# EaglePCBWorkshop.net
KiCad netlist of a schematic drawn in EAGLE
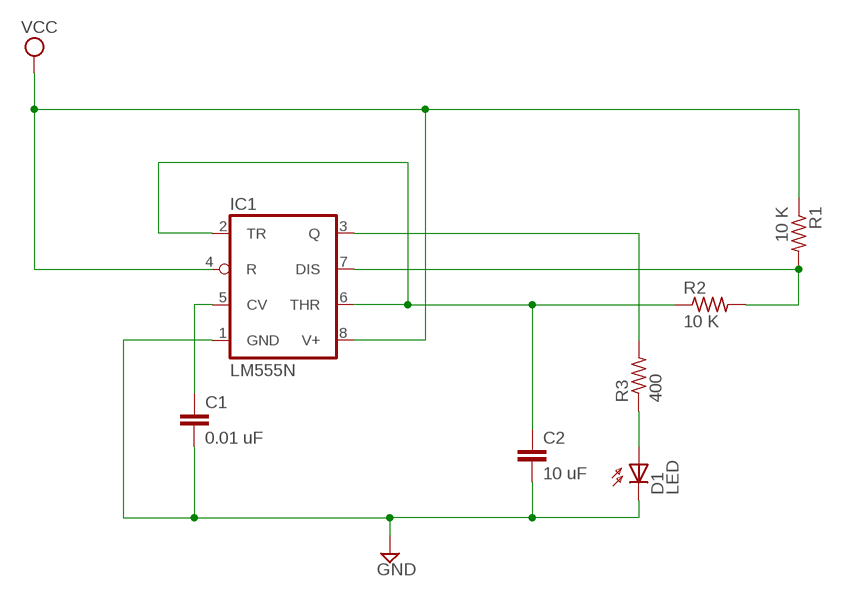
[diagram p0: schematic, sheet 1]

(export (version "E")
  (design (tool "Eeschema 10.0.6"))
  (components
    (comp (ref "C1")
      (value "0.01 uF")
      (footprint "eagle-import:C5B2.5")
      (libsource (lib "eagle-import") (part "C5/2.5"))
    )
    (comp (ref "C2")
      (value "10 uF")
      (footprint "eagle-import:C5B2.5")
      (libsource (lib "eagle-import") (part "C5/2.5"))
    )
    (comp (ref "D1")
      (value "LED")
      (footprint "eagle-import:SFH205")
      (libsource (lib "eagle-import") (part "SFH205"))
    )
    (comp (ref "IC1")
      (value "LM555N")
      (footprint "eagle-import:DIL08")
      (libsource (lib "eagle-import") (part "555NLM"))
    )
    (comp (ref "R1")
      (value "10 K")
      (footprint "eagle-import:0204_7")
      (libsource (lib "eagle-import") (part "R-US_0204/7"))
    )
    (comp (ref "R2")
      (value "10 K")
      (footprint "eagle-import:0204_7")
      (libsource (lib "eagle-import") (part "R-US_0204/7"))
    )
    (comp (ref "R3")
      (value "400")
      (footprint "eagle-import:0204_7")
      (libsource (lib "eagle-import") (part "R-US_0204/7"))
    )
  )
  (nets
    (net (code "1") (name "GND") (class "Default")
      (node (ref "C1") (pin "2") (pinfunction "2_2") (pintype "passive"))
      (node (ref "C2") (pin "2") (pinfunction "2_2") (pintype "passive"))
      (node (ref "D1") (pin "K") (pinfunction "C_K") (pintype "passive"))
      (node (ref "IC1") (pin "1") (pinfunction "GND_1") (pintype "power_in"))
    )
    (net (code "2") (name "Net-(D1-PadA)") (class "Default")
      (node (ref "D1") (pin "A") (pinfunction "A_A") (pintype "passive"))
      (node (ref "R3") (pin "1") (pinfunction "1_1") (pintype "passive"))
    )
    (net (code "3") (name "Net-(IC1-CV)") (class "Default")
      (node (ref "C1") (pin "1") (pinfunction "1_1") (pintype "passive"))
      (node (ref "IC1") (pin "5") (pinfunction "CV_5") (pintype "input"))
    )
    (net (code "4") (name "Net-(IC1-DIS)") (class "Default")
      (node (ref "IC1") (pin "7") (pinfunction "DIS_7") (pintype "input"))
      (node (ref "R1") (pin "2") (pinfunction "2_2") (pintype "passive"))
      (node (ref "R2") (pin "2") (pinfunction "2_2") (pintype "passive"))
    )
    (net (code "5") (name "Net-(IC1-Q)") (class "Default")
      (node (ref "IC1") (pin "3") (pinfunction "Q_3") (pintype "output"))
      (node (ref "R3") (pin "2") (pinfunction "2_2") (pintype "passive"))
    )
    (net (code "6") (name "Net-(IC1-THR)") (class "Default")
      (node (ref "C2") (pin "1") (pinfunction "1_1") (pintype "passive"))
      (node (ref "IC1") (pin "2") (pinfunction "TR_2") (pintype "input"))
      (node (ref "IC1") (pin "6") (pinfunction "THR_6") (pintype "input"))
      (node (ref "R2") (pin "1") (pinfunction "1_1") (pintype "passive"))
    )
    (net (code "7") (name "VCC") (class "Default")
      (node (ref "IC1") (pin "4") (pinfunction "R_4") (pintype "input"))
      (node (ref "IC1") (pin "8") (pinfunction "V+_8") (pintype "power_in"))
      (node (ref "R1") (pin "1") (pinfunction "1_1") (pintype "passive"))
    )
  )
)
